# LipSync_Interface_Board_March_8.net
KiCad netlist of a schematic drawn in EAGLE
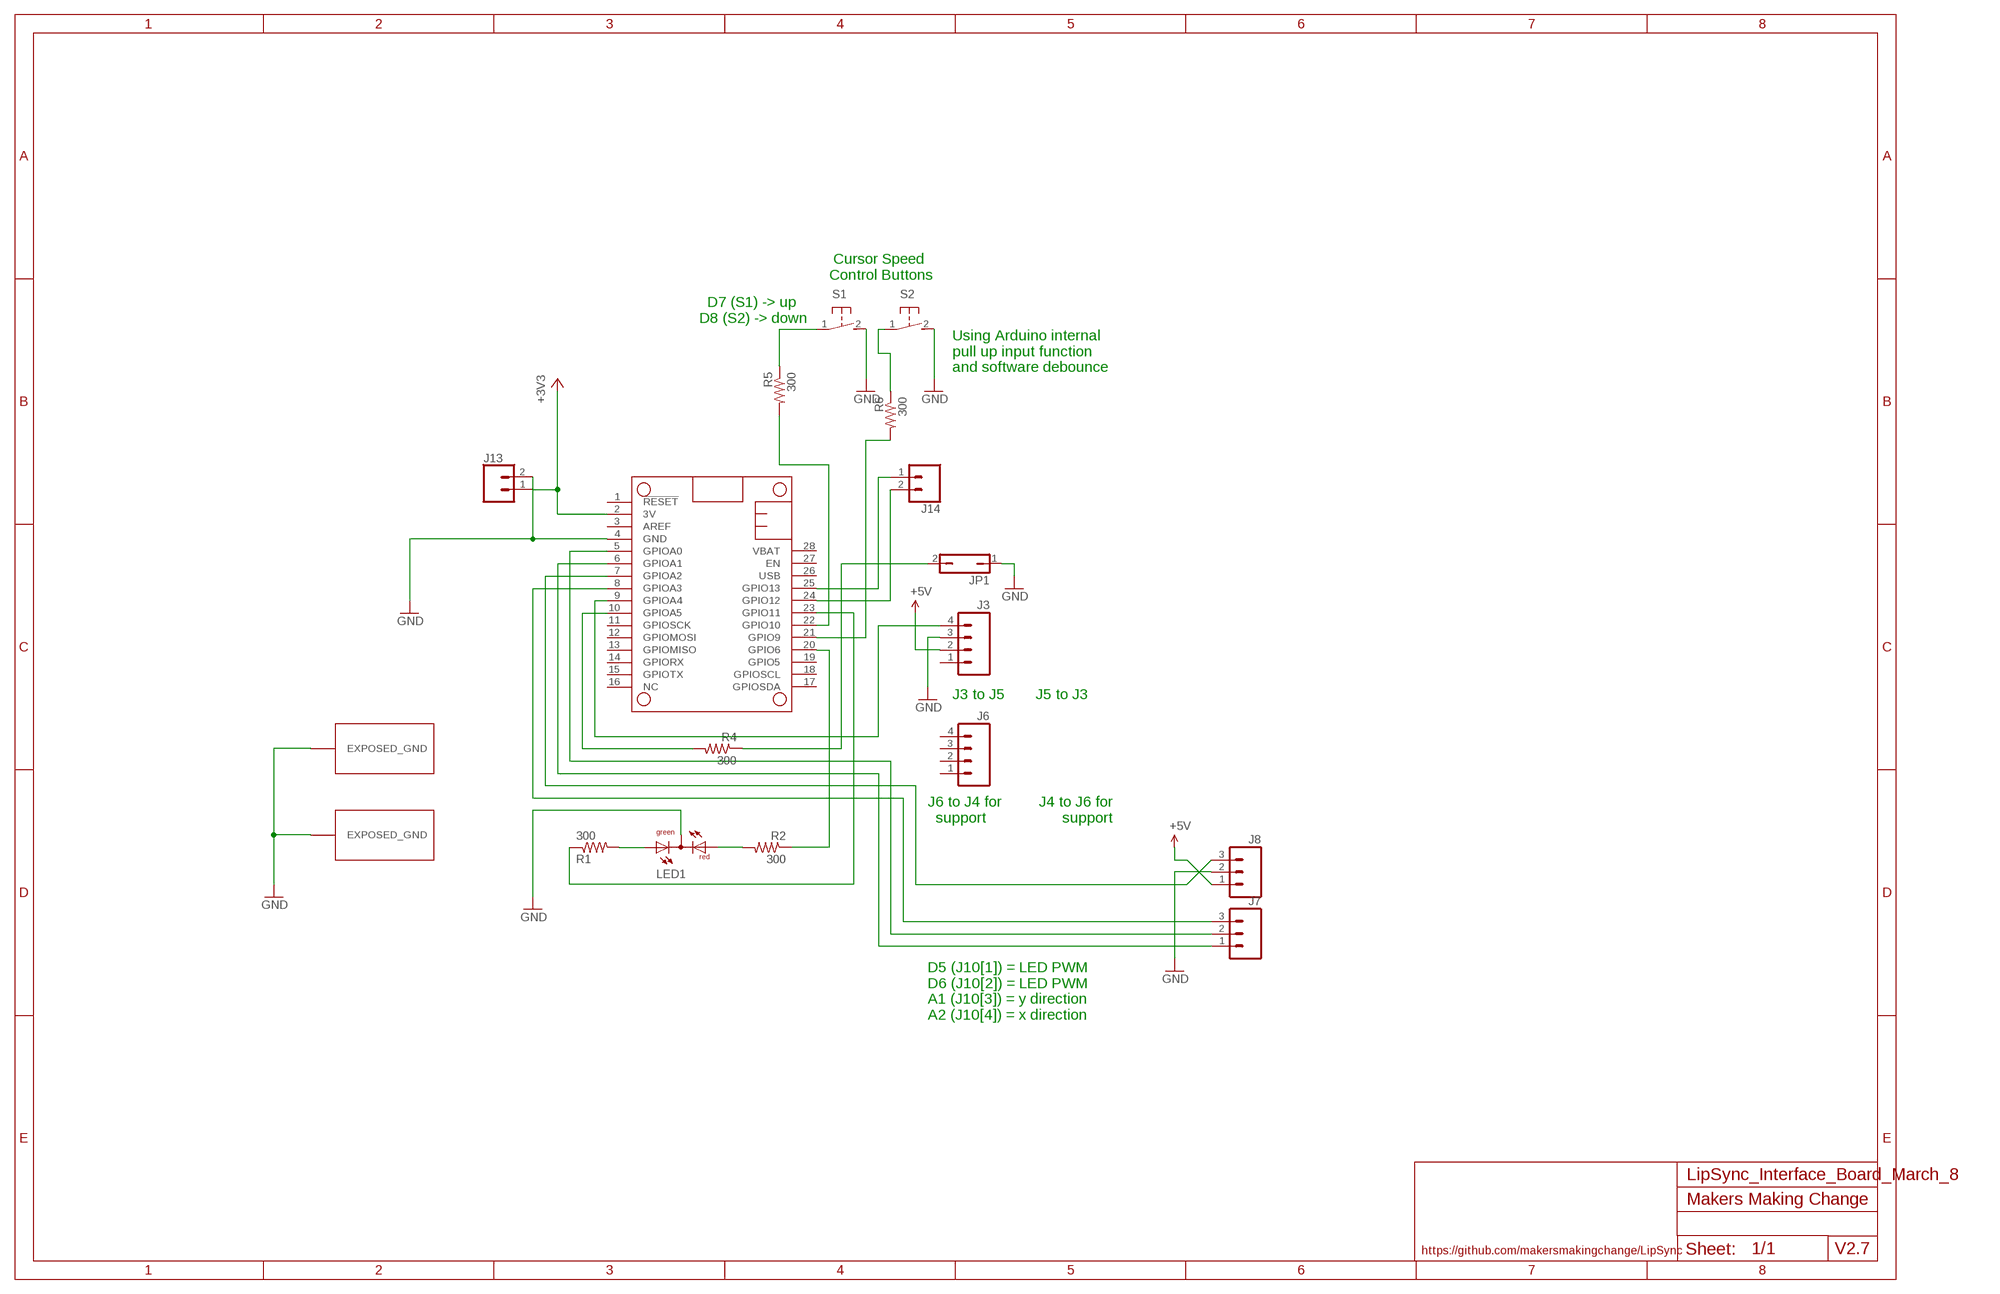
[diagram p0: schematic, sheet 1]

(export (version "E")
  (design (tool "Eeschema 10.0.6"))
  (components
    (comp (ref "J3")
      (value "M04PTH")
      (footprint "eagle-import:1X04")
      (libsource (lib "eagle-import") (part "M04PTH"))
    )
    (comp (ref "J6")
      (value "M04PTH")
      (footprint "eagle-import:1X04")
      (libsource (lib "eagle-import") (part "M04PTH"))
    )
    (comp (ref "J7")
      (value "M03LOCK")
      (footprint "eagle-import:1X03_LOCK")
      (libsource (lib "eagle-import") (part "M03LOCK"))
    )
    (comp (ref "J8")
      (value "M03LOCK")
      (footprint "eagle-import:1X03_LOCK")
      (libsource (lib "eagle-import") (part "M03LOCK"))
    )
    (comp (ref "J13")
      (value "CONN_02")
      (footprint "eagle-import:1X02")
      (libsource (lib "eagle-import") (part "CONN_02"))
    )
    (comp (ref "J14")
      (value "CONN_02")
      (footprint "eagle-import:1X02")
      (libsource (lib "eagle-import") (part "CONN_02"))
    )
    (comp (ref "JP1")
      (value "JP1Q")
      (footprint "eagle-import:JP1")
      (libsource (lib "eagle-import") (part "JP1Q"))
    )
    (comp (ref "LED1")
      (value "DUOLED-RG-C")
      (footprint "eagle-import:DUOLED-C-5MM")
      (libsource (lib "eagle-import") (part "DUOLED-RG-C"))
    )
    (comp (ref "MS2")
      (value "FEATHERWING_NODIM")
      (footprint "eagle-import:FEATHERWING_DIM")
      (libsource (lib "eagle-import") (part "FEATHERWING_NODIM"))
    )
    (comp (ref "R1")
      (value "300")
      (footprint "eagle-import:AXIAL-0.3")
      (libsource (lib "eagle-import") (part "RESISTORAXIAL-0.3"))
    )
    (comp (ref "R2")
      (value "300")
      (footprint "eagle-import:AXIAL-0.3")
      (libsource (lib "eagle-import") (part "RESISTORAXIAL-0.3"))
    )
    (comp (ref "R4")
      (value "300")
      (footprint "eagle-import:AXIAL-0.3")
      (libsource (lib "eagle-import") (part "RESISTORAXIAL-0.3"))
    )
    (comp (ref "R5")
      (value "300")
      (footprint "eagle-import:AXIAL-0.3")
      (libsource (lib "eagle-import") (part "RESISTORAXIAL-0.3"))
    )
    (comp (ref "R6")
      (value "300")
      (footprint "eagle-import:AXIAL-0.3")
      (libsource (lib "eagle-import") (part "RESISTORAXIAL-0.3"))
    )
    (comp (ref "S1")
      (value "31-XXB3F-31XX-CUSTOM")
      (footprint "eagle-import:B3F-31XX-CUSTOM")
      (libsource (lib "eagle-import") (part "31-XXB3F-31XX-CUSTOM"))
    )
    (comp (ref "S2")
      (value "31-XXB3F-31XX-CUSTOM")
      (footprint "eagle-import:B3F-31XX-CUSTOM")
      (libsource (lib "eagle-import") (part "31-XXB3F-31XX-CUSTOM"))
    )
    (comp (ref "U$2")
      (value "EXPOSED_GND")
      (footprint "eagle-import:EXPOSED_GND")
      (libsource (lib "eagle-import") (part "EXPOSED_GND"))
    )
    (comp (ref "U$3")
      (value "EXPOSED_GND")
      (footprint "eagle-import:EXPOSED_GND")
      (libsource (lib "eagle-import") (part "EXPOSED_GND"))
    )
  )
  (nets
    (net (code "1") (name "+3V3") (class "Default")
      (node (ref "J13") (pin "1") (pinfunction "1_1") (pintype "passive"))
      (node (ref "MS2") (pin "2") (pinfunction "3V_2") (pintype "power_in"))
    )
    (net (code "2") (name "+5V") (class "Default")
      (node (ref "J3") (pin "2") (pinfunction "2_2") (pintype "passive"))
      (node (ref "J8") (pin "1") (pinfunction "1_1") (pintype "passive"))
    )
    (net (code "3") (name "/USB") (class "Default")
      (node (ref "MS2") (pin "26") (pinfunction "USB_26") (pintype "power_in"))
    )
    (net (code "4") (name "/VBAT") (class "Default")
      (node (ref "MS2") (pin "28") (pinfunction "VBAT_28") (pintype "power_in"))
    )
    (net (code "5") (name "EXPOSED_GND") (class "Default")
      (node (ref "J13") (pin "2") (pinfunction "2_2") (pintype "passive"))
      (node (ref "J3") (pin "3") (pinfunction "3_3") (pintype "passive"))
      (node (ref "J8") (pin "2") (pinfunction "2_2") (pintype "passive"))
      (node (ref "JP1") (pin "1") (pinfunction "1_1") (pintype "passive"))
      (node (ref "LED1") (pin "C") (pinfunction "C_C") (pintype "passive"))
      (node (ref "MS2") (pin "4") (pinfunction "GND_4") (pintype "power_in"))
      (node (ref "S1") (pin "2") (pinfunction "S_2") (pintype "passive"))
      (node (ref "S2") (pin "2") (pinfunction "S_2") (pintype "passive"))
      (node (ref "U$2") (pin "GND1") (pinfunction "EXPOSED_GND_GND1") (pintype "power_in"))
      (node (ref "U$3") (pin "GND1") (pinfunction "EXPOSED_GND_GND1") (pintype "power_in"))
    )
    (net (code "6") (name "Net-(LED1-AG)") (class "Default")
      (node (ref "LED1") (pin "AX") (pinfunction "AG_AX") (pintype "passive"))
      (node (ref "R1") (pin "P$2") (pinfunction "2_P$2") (pintype "passive"))
    )
    (net (code "7") (name "Net-(MS2-GPIO6)") (class "Default")
      (node (ref "MS2") (pin "20") (pinfunction "GPIO6_20") (pintype "bidirectional"))
      (node (ref "R2") (pin "P$1") (pinfunction "1_P$1") (pintype "passive"))
    )
    (net (code "8") (name "Net-(MS2-GPIO9)") (class "Default")
      (node (ref "MS2") (pin "21") (pinfunction "GPIO9_21") (pintype "bidirectional"))
      (node (ref "R6") (pin "P$2") (pinfunction "2_P$2") (pintype "passive"))
    )
    (net (code "9") (name "Net-(MS2-GPIO10)") (class "Default")
      (node (ref "MS2") (pin "22") (pinfunction "GPIO10_22") (pintype "bidirectional"))
      (node (ref "R5") (pin "P$2") (pinfunction "2_P$2") (pintype "passive"))
    )
    (net (code "10") (name "Net-(MS2-GPIO11)") (class "Default")
      (node (ref "MS2") (pin "23") (pinfunction "GPIO11_23") (pintype "bidirectional"))
      (node (ref "R1") (pin "P$1") (pinfunction "1_P$1") (pintype "passive"))
    )
    (net (code "11") (name "Net-(MS2-GPIO12)") (class "Default")
      (node (ref "J14") (pin "2") (pinfunction "2_2") (pintype "passive"))
      (node (ref "MS2") (pin "24") (pinfunction "GPIO12_24") (pintype "bidirectional"))
    )
    (net (code "12") (name "Net-(MS2-GPIO13)") (class "Default")
      (node (ref "J14") (pin "1") (pinfunction "1_1") (pintype "passive"))
      (node (ref "MS2") (pin "25") (pinfunction "GPIO13_25") (pintype "bidirectional"))
    )
    (net (code "13") (name "Net-(MS2-GPIOA0)") (class "Default")
      (node (ref "J7") (pin "2") (pinfunction "2_2") (pintype "passive"))
      (node (ref "MS2") (pin "5") (pinfunction "GPIOA0_5") (pintype "bidirectional"))
    )
    (net (code "14") (name "Net-(MS2-GPIOA1)") (class "Default")
      (node (ref "J7") (pin "1") (pinfunction "1_1") (pintype "passive"))
      (node (ref "MS2") (pin "6") (pinfunction "GPIOA1_6") (pintype "bidirectional"))
    )
    (net (code "15") (name "Net-(MS2-GPIOA2)") (class "Default")
      (node (ref "J8") (pin "3") (pinfunction "3_3") (pintype "passive"))
      (node (ref "MS2") (pin "7") (pinfunction "GPIOA2_7") (pintype "bidirectional"))
    )
    (net (code "16") (name "Net-(MS2-GPIOA3)") (class "Default")
      (node (ref "J7") (pin "3") (pinfunction "3_3") (pintype "passive"))
      (node (ref "MS2") (pin "8") (pinfunction "GPIOA3_8") (pintype "bidirectional"))
    )
    (net (code "17") (name "Net-(MS2-GPIOA4)") (class "Default")
      (node (ref "J3") (pin "4") (pinfunction "4_4") (pintype "passive"))
      (node (ref "MS2") (pin "9") (pinfunction "GPIOA4_9") (pintype "bidirectional"))
    )
    (net (code "18") (name "Net-(MS2-GPIOA5)") (class "Default")
      (node (ref "MS2") (pin "10") (pinfunction "GPIOA5_10") (pintype "bidirectional"))
      (node (ref "R4") (pin "P$2") (pinfunction "2_P$2") (pintype "passive"))
    )
    (net (code "19") (name "Net-(R2-2)") (class "Default")
      (node (ref "LED1") (pin "AR") (pinfunction "AR_AR") (pintype "passive"))
      (node (ref "R2") (pin "P$2") (pinfunction "2_P$2") (pintype "passive"))
    )
    (net (code "20") (name "Net-(R4-1)") (class "Default")
      (node (ref "JP1") (pin "2") (pinfunction "2_2") (pintype "passive"))
      (node (ref "R4") (pin "P$1") (pinfunction "1_P$1") (pintype "passive"))
    )
    (net (code "21") (name "Net-(R5-1)") (class "Default")
      (node (ref "R5") (pin "P$1") (pinfunction "1_P$1") (pintype "passive"))
      (node (ref "S1") (pin "1") (pinfunction "P_1") (pintype "passive"))
    )
    (net (code "22") (name "Net-(R6-1)") (class "Default")
      (node (ref "R6") (pin "P$1") (pinfunction "1_P$1") (pintype "passive"))
      (node (ref "S2") (pin "1") (pinfunction "P_1") (pintype "passive"))
    )
    (net (code "23") (name "unconnected-(J3-Pad1)") (class "Default")
      (node (ref "J3") (pin "1") (pinfunction "1_1") (pintype "passive"))
    )
    (net (code "24") (name "unconnected-(J6-Pad1)") (class "Default")
      (node (ref "J6") (pin "1") (pinfunction "1_1") (pintype "passive"))
    )
    (net (code "25") (name "unconnected-(J6-Pad2)") (class "Default")
      (node (ref "J6") (pin "2") (pinfunction "2_2") (pintype "passive"))
    )
    (net (code "26") (name "unconnected-(J6-Pad3)") (class "Default")
      (node (ref "J6") (pin "3") (pinfunction "3_3") (pintype "passive"))
    )
    (net (code "27") (name "unconnected-(J6-Pad4)") (class "Default")
      (node (ref "J6") (pin "4") (pinfunction "4_4") (pintype "passive"))
    )
    (net (code "28") (name "unconnected-(MS2-AREF-Pad3)") (class "Default")
      (node (ref "MS2") (pin "3") (pinfunction "AREF_3") (pintype "passive"))
    )
    (net (code "29") (name "unconnected-(MS2-EN-Pad27)") (class "Default")
      (node (ref "MS2") (pin "27") (pinfunction "EN_27") (pintype "passive"))
    )
    (net (code "30") (name "unconnected-(MS2-GPIO5-Pad19)") (class "Default")
      (node (ref "MS2") (pin "19") (pinfunction "GPIO5_19") (pintype "bidirectional"))
    )
    (net (code "31") (name "unconnected-(MS2-GPIOMISO-Pad13)") (class "Default")
      (node (ref "MS2") (pin "13") (pinfunction "GPIOMISO_13") (pintype "bidirectional"))
    )
    (net (code "32") (name "unconnected-(MS2-GPIOMOSI-Pad12)") (class "Default")
      (node (ref "MS2") (pin "12") (pinfunction "GPIOMOSI_12") (pintype "bidirectional"))
    )
    (net (code "33") (name "unconnected-(MS2-GPIORX-Pad14)") (class "Default")
      (node (ref "MS2") (pin "14") (pinfunction "GPIORX_14") (pintype "bidirectional"))
    )
    (net (code "34") (name "unconnected-(MS2-GPIOSCK-Pad11)") (class "Default")
      (node (ref "MS2") (pin "11") (pinfunction "GPIOSCK_11") (pintype "bidirectional"))
    )
    (net (code "35") (name "unconnected-(MS2-GPIOSCL-Pad18)") (class "Default")
      (node (ref "MS2") (pin "18") (pinfunction "GPIOSCL_18") (pintype "bidirectional"))
    )
    (net (code "36") (name "unconnected-(MS2-GPIOSDA-Pad17)") (class "Default")
      (node (ref "MS2") (pin "17") (pinfunction "GPIOSDA_17") (pintype "bidirectional"))
    )
    (net (code "37") (name "unconnected-(MS2-GPIOTX-Pad15)") (class "Default")
      (node (ref "MS2") (pin "15") (pinfunction "GPIOTX_15") (pintype "bidirectional"))
    )
    (net (code "38") (name "unconnected-(MS2-NC-Pad16)") (class "Default")
      (node (ref "MS2") (pin "16") (pinfunction "NC_16") (pintype "passive"))
    )
    (net (code "39") (name "unconnected-(MS2-~{RESET}-Pad1)") (class "Default")
      (node (ref "MS2") (pin "1") (pinfunction "~{RESET}_1") (pintype "input"))
    )
  )
)
